# jtag.net
KiCad netlist of a schematic drawn in Altium Designer
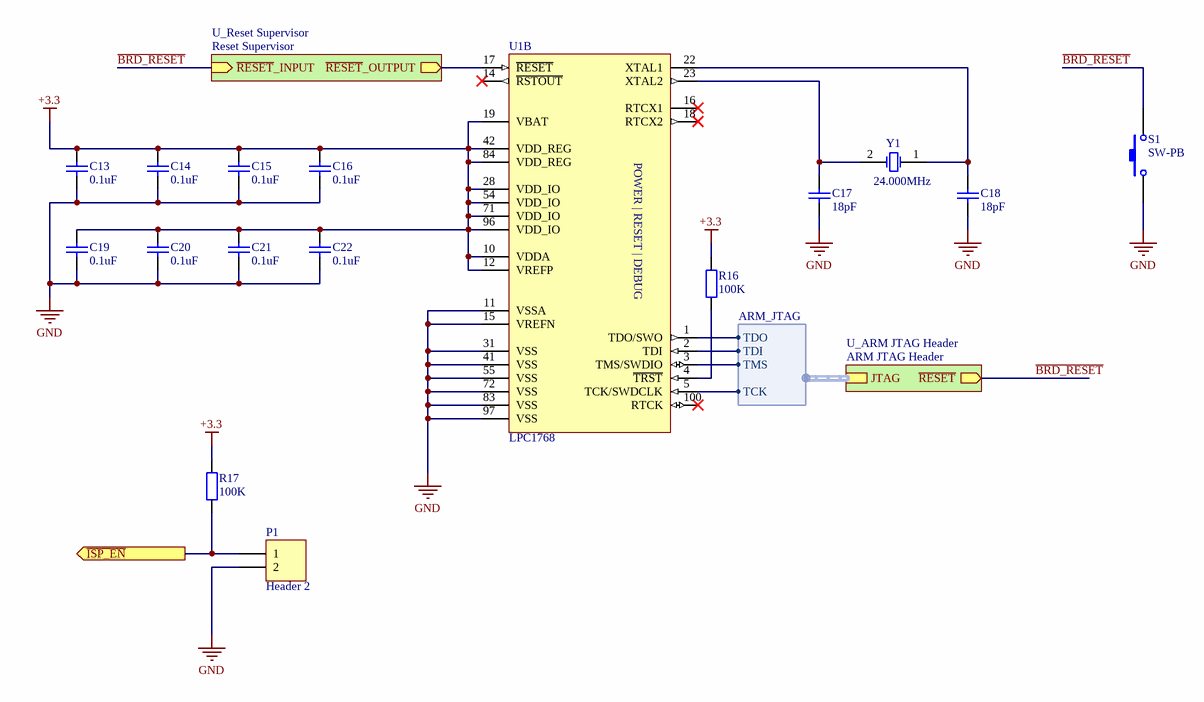
[diagram p0: jtag.SchDoc]

(export (version "E")
  (design (tool "Eeschema 10.0.6"))
  (components
    (comp (ref "C13")
      (value "0.1uF")
      (footprint "C0603")
      (description "Capacitor")
      (fields (field (name "Comment") "Cap"))
      (libsource (lib "Miscellaneous Devices") (part "Cap"))
    )
    (comp (ref "C14")
      (value "0.1uF")
      (footprint "C0603")
      (description "Capacitor")
      (fields (field (name "Comment") "Cap"))
      (libsource (lib "Miscellaneous Devices") (part "Cap"))
    )
    (comp (ref "C15")
      (value "0.1uF")
      (footprint "C0603")
      (description "Capacitor")
      (fields (field (name "Comment") "Cap"))
      (libsource (lib "Miscellaneous Devices") (part "Cap"))
    )
    (comp (ref "C16")
      (value "0.1uF")
      (footprint "C0603")
      (description "Capacitor")
      (fields (field (name "Comment") "Cap"))
      (libsource (lib "Miscellaneous Devices") (part "Cap"))
    )
    (comp (ref "C17")
      (value "18pF")
      (footprint "C0603")
      (description "Capacitor")
      (fields (field (name "Comment") "Cap"))
      (libsource (lib "Miscellaneous Devices") (part "Cap"))
    )
    (comp (ref "C18")
      (value "18pF")
      (footprint "C0603")
      (description "Capacitor")
      (fields (field (name "Comment") "Cap"))
      (libsource (lib "Miscellaneous Devices") (part "Cap"))
    )
    (comp (ref "C19")
      (value "0.1uF")
      (footprint "C0603")
      (description "Capacitor")
      (fields (field (name "Comment") "Cap"))
      (libsource (lib "Miscellaneous Devices") (part "Cap"))
    )
    (comp (ref "C20")
      (value "0.1uF")
      (footprint "C0603")
      (description "Capacitor")
      (fields (field (name "Comment") "Cap"))
      (libsource (lib "Miscellaneous Devices") (part "Cap"))
    )
    (comp (ref "C21")
      (value "0.1uF")
      (footprint "C0603")
      (description "Capacitor")
      (fields (field (name "Comment") "Cap"))
      (libsource (lib "Miscellaneous Devices") (part "Cap"))
    )
    (comp (ref "C22")
      (value "0.1uF")
      (footprint "C0603")
      (description "Capacitor")
      (fields (field (name "Comment") "Cap"))
      (libsource (lib "Miscellaneous Devices") (part "Cap"))
    )
    (comp (ref "P1")
      (value "Header 2")
      (footprint "HDR1X2")
      (description "Header, 2-Pin")
      (fields (field (name "PUBLISHER") "Altium Limited"))
      (libsource (lib "Miscellaneous Connectors") (part "Header 2"))
    )
    (comp (ref "R16")
      (value "100K")
      (footprint "R0603")
      (description "Resistor")
      (fields (field (name "Comment") "Res"))
      (libsource (lib "Miscellaneous Devices") (part "Res2"))
    )
    (comp (ref "R17")
      (value "100K")
      (footprint "R0603")
      (description "Resistor")
      (fields (field (name "Comment") "Res"))
      (libsource (lib "Miscellaneous Devices") (part "Res2"))
    )
    (comp (ref "S1")
      (value "SW-PB")
      (footprint "DTSM-32S-B")
      (description "Switch")
      (fields (field (name "PUBLISHER") "Altium Limited"))
      (libsource (lib "Miscellaneous Devices") (part "SW-PB"))
    )
    (comp (ref "U1") (value "LPC1768") (footprint "LPC1768") (libsource (lib "mcb") (part "LPC1768")))
    (comp (ref "Y1")
      (value "24.000MHz")
      (footprint "C3E-24.000-12-3030-X")
      (description "Crystal Oscillator")
      (fields (field (name "Comment") "XTAL"))
      (libsource (lib "Miscellaneous Devices") (part "XTAL"))
    )
  )
  (nets
    (net (code "2") (name "+3.3") (class "Default")
      (node (ref "C13") (pin "1") (pinfunction "1_1") (pintype "passive"))
      (node (ref "C14") (pin "1") (pinfunction "1_1") (pintype "passive"))
      (node (ref "C15") (pin "1") (pinfunction "1_1") (pintype "passive"))
      (node (ref "C16") (pin "1") (pinfunction "1_1") (pintype "passive"))
      (node (ref "C19") (pin "1") (pinfunction "1_1") (pintype "passive"))
      (node (ref "C20") (pin "1") (pinfunction "1_1") (pintype "passive"))
      (node (ref "C21") (pin "1") (pinfunction "1_1") (pintype "passive"))
      (node (ref "C22") (pin "1") (pinfunction "1_1") (pintype "passive"))
      (node (ref "R16") (pin "2") (pinfunction "2_2") (pintype "passive"))
      (node (ref "R17") (pin "2") (pinfunction "2_2") (pintype "passive"))
      (node (ref "U1") (pin "10") (pinfunction "VDDA_10") (pintype "power_in"))
      (node (ref "U1") (pin "12") (pinfunction "VREFP_12") (pintype "passive"))
      (node (ref "U1") (pin "19") (pinfunction "VBAT_19") (pintype "power_in"))
      (node (ref "U1") (pin "28") (pinfunction "VDD_IO_28") (pintype "power_in"))
      (node (ref "U1") (pin "42") (pinfunction "VDD_REG_42") (pintype "power_in"))
      (node (ref "U1") (pin "54") (pinfunction "VDD_IO_54") (pintype "power_in"))
      (node (ref "U1") (pin "71") (pinfunction "VDD_IO_71") (pintype "power_in"))
      (node (ref "U1") (pin "84") (pinfunction "VDD_REG_84") (pintype "power_in"))
      (node (ref "U1") (pin "96") (pinfunction "VDD_IO_96") (pintype "power_in"))
    )
    (net (code "3") (name "/TCK") (class "Default")
      (node (ref "U1") (pin "5") (pinfunction "TCK/SWDCLK_5") (pintype "input"))
    )
    (net (code "4") (name "/TDI") (class "Default")
      (node (ref "U1") (pin "2") (pinfunction "TDI_2") (pintype "input"))
    )
    (net (code "5") (name "/TDO") (class "Default")
      (node (ref "U1") (pin "1") (pinfunction "TDO/SWO_1") (pintype "output"))
    )
    (net (code "6") (name "/TMS") (class "Default")
      (node (ref "U1") (pin "3") (pinfunction "TMS/SWDIO_3") (pintype "bidirectional"))
    )
    (net (code "8") (name "/~{BRD_RESET}") (class "Default")
      (node (ref "S1") (pin "2") (pinfunction "2_2") (pintype "passive"))
    )
    (net (code "9") (name "/~{ISP_EN}") (class "Default")
      (node (ref "P1") (pin "1") (pinfunction "1_1") (pintype "passive"))
      (node (ref "R17") (pin "1") (pinfunction "1_1") (pintype "passive"))
    )
    (net (code "10") (name "/~{RESET}_OUTPUT") (class "Default")
      (node (ref "U1") (pin "17") (pinfunction "~{RESET}_17") (pintype "input"))
    )
    (net (code "11") (name "GND") (class "Default")
      (node (ref "C13") (pin "2") (pinfunction "2_2") (pintype "passive"))
      (node (ref "C14") (pin "2") (pinfunction "2_2") (pintype "passive"))
      (node (ref "C15") (pin "2") (pinfunction "2_2") (pintype "passive"))
      (node (ref "C16") (pin "2") (pinfunction "2_2") (pintype "passive"))
      (node (ref "C17") (pin "2") (pinfunction "2_2") (pintype "passive"))
      (node (ref "C18") (pin "2") (pinfunction "2_2") (pintype "passive"))
      (node (ref "C19") (pin "2") (pinfunction "2_2") (pintype "passive"))
      (node (ref "C20") (pin "2") (pinfunction "2_2") (pintype "passive"))
      (node (ref "C21") (pin "2") (pinfunction "2_2") (pintype "passive"))
      (node (ref "C22") (pin "2") (pinfunction "2_2") (pintype "passive"))
      (node (ref "P1") (pin "2") (pinfunction "2_2") (pintype "passive"))
      (node (ref "S1") (pin "1") (pinfunction "1_1") (pintype "passive"))
      (node (ref "U1") (pin "11") (pinfunction "VSSA_11") (pintype "power_in"))
      (node (ref "U1") (pin "15") (pinfunction "VREFN_15") (pintype "passive"))
      (node (ref "U1") (pin "31") (pinfunction "VSS_31") (pintype "power_in"))
      (node (ref "U1") (pin "41") (pinfunction "VSS_41") (pintype "power_in"))
      (node (ref "U1") (pin "55") (pinfunction "VSS_55") (pintype "power_in"))
      (node (ref "U1") (pin "72") (pinfunction "VSS_72") (pintype "power_in"))
      (node (ref "U1") (pin "83") (pinfunction "VSS_83") (pintype "power_in"))
      (node (ref "U1") (pin "97") (pinfunction "VSS_97") (pintype "power_in"))
    )
    (net (code "12") (name "Net-(U1B-XTAL1)") (class "Default")
      (node (ref "C18") (pin "1") (pinfunction "1_1") (pintype "passive"))
      (node (ref "U1") (pin "22") (pinfunction "XTAL1_22") (pintype "passive"))
      (node (ref "Y1") (pin "1") (pinfunction "OSC1_1") (pintype "passive"))
    )
    (net (code "13") (name "Net-(U1B-XTAL2)") (class "Default")
      (node (ref "C17") (pin "1") (pinfunction "1_1") (pintype "passive"))
      (node (ref "U1") (pin "23") (pinfunction "XTAL2_23") (pintype "output"))
      (node (ref "Y1") (pin "2") (pinfunction "OSC2_2") (pintype "passive"))
    )
    (net (code "14") (name "Net-(U1B-~{TRST})") (class "Default")
      (node (ref "R16") (pin "1") (pinfunction "1_1") (pintype "passive"))
      (node (ref "U1") (pin "4") (pinfunction "~{TRST}_4") (pintype "input"))
    )
    (net (code "15") (name "unconnected-(U1B-RTCK-Pad100)") (class "Default")
      (node (ref "U1") (pin "100") (pinfunction "RTCK_100") (pintype "bidirectional+no_connect"))
    )
    (net (code "16") (name "unconnected-(U1B-RTCX1-Pad16)") (class "Default")
      (node (ref "U1") (pin "16") (pinfunction "RTCX1_16") (pintype "passive+no_connect"))
    )
    (net (code "17") (name "unconnected-(U1B-RTCX2-Pad18)") (class "Default")
      (node (ref "U1") (pin "18") (pinfunction "RTCX2_18") (pintype "output+no_connect"))
    )
    (net (code "18") (name "unconnected-(U1B-~{RSTOUT}-Pad14)") (class "Default")
      (node (ref "U1") (pin "14") (pinfunction "~{RSTOUT}_14") (pintype "output+no_connect"))
    )
  )
)
